# 05_RADIO.net
KiCad netlist of a schematic drawn in Altium Designer
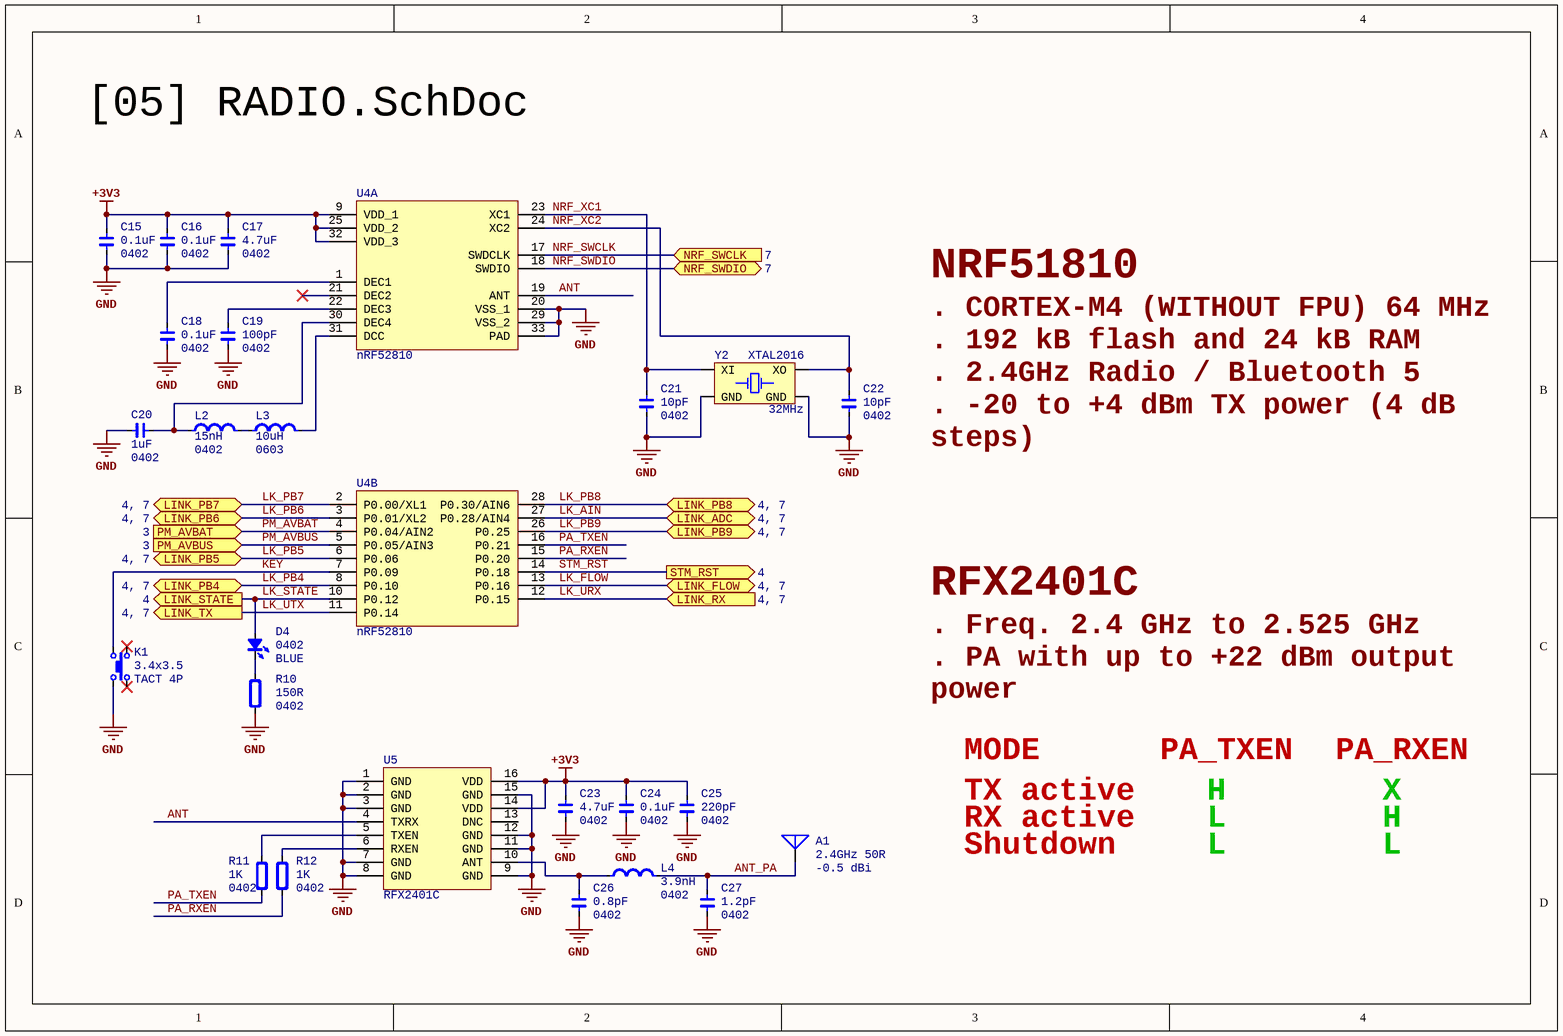
[diagram p0: [05] RADIO.SchDoc]

(export (version "E")
  (design (tool "Eeschema 10.0.6"))
  (components
    (comp (ref "A1")
      (value "2.4GHz 50R")
      (footprint "PCB_Antenna:ANT_2.4G_3.2x1.6")
      (description "Antenna")
      (fields (field (name "ALTIUM_VALUE") "-0.5 dBi"))
      (libsource (lib "SCH_Antenna") (part "Ant_2.4G"))
    )
    (comp (ref "C15")
      (value "0.1uF")
      (footprint "PCB_PassiveCap:CAP_0402")
      (description "Capacitor")
      (fields (field (name "TYPE") "0402") (field (name "Comment") "C0402"))
      (libsource (lib "SCH_Passive") (part "Cap_0402"))
    )
    (comp (ref "C16")
      (value "0.1uF")
      (footprint "PCB_PassiveCap:CAP_0402")
      (description "Capacitor")
      (fields (field (name "TYPE") "0402") (field (name "Comment") "C0402"))
      (libsource (lib "SCH_Passive") (part "Cap_0402"))
    )
    (comp (ref "C17")
      (value "4.7uF")
      (footprint "PCB_PassiveCap:CAP_0402")
      (description "Capacitor")
      (fields (field (name "TYPE") "0402") (field (name "Comment") "C0402"))
      (libsource (lib "SCH_Passive") (part "Cap_0402"))
    )
    (comp (ref "C18")
      (value "0.1uF")
      (footprint "PCB_PassiveCap:CAP_0402")
      (description "Capacitor")
      (fields (field (name "TYPE") "0402") (field (name "Comment") "C0402"))
      (libsource (lib "SCH_Passive") (part "Cap_0402"))
    )
    (comp (ref "C19")
      (value "100pF")
      (footprint "PCB_PassiveCap:CAP_0402")
      (description "Capacitor")
      (fields (field (name "TYPE") "0402") (field (name "Comment") "C0402"))
      (libsource (lib "SCH_Passive") (part "Cap_0402"))
    )
    (comp (ref "C20")
      (value "1uF")
      (footprint "PCB_PassiveCap:CAP_0402")
      (description "Capacitor")
      (fields (field (name "TYPE") "0402") (field (name "Comment") "C0402"))
      (libsource (lib "") (part "Cap_0402_1"))
    )
    (comp (ref "C21")
      (value "10pF")
      (footprint "PCB_PassiveCap:CAP_0402")
      (description "Capacitor")
      (fields (field (name "TYPE") "0402") (field (name "Comment") "C0402"))
      (libsource (lib "SCH_Passive") (part "Cap_0402"))
    )
    (comp (ref "C22")
      (value "10pF")
      (footprint "PCB_PassiveCap:CAP_0402")
      (description "Capacitor")
      (fields (field (name "TYPE") "0402") (field (name "Comment") "C0402"))
      (libsource (lib "SCH_Passive") (part "Cap_0402"))
    )
    (comp (ref "C23")
      (value "4.7uF")
      (footprint "PCB_PassiveCap:CAP_0402")
      (description "Capacitor")
      (fields (field (name "TYPE") "0402") (field (name "Comment") "C0402"))
      (libsource (lib "SCH_Passive") (part "Cap_0402"))
    )
    (comp (ref "C24")
      (value "0.1uF")
      (footprint "PCB_PassiveCap:CAP_0402")
      (description "Capacitor")
      (fields (field (name "TYPE") "0402") (field (name "Comment") "C0402"))
      (libsource (lib "SCH_Passive") (part "Cap_0402"))
    )
    (comp (ref "C25")
      (value "220pF")
      (footprint "PCB_PassiveCap:CAP_0402")
      (description "Capacitor")
      (fields (field (name "TYPE") "0402") (field (name "Comment") "C0402"))
      (libsource (lib "SCH_Passive") (part "Cap_0402"))
    )
    (comp (ref "C26")
      (value "0.8pF")
      (footprint "PCB_PassiveCap:CAP_0402")
      (description "Capacitor")
      (fields (field (name "TYPE") "0402") (field (name "Comment") "C0402"))
      (libsource (lib "SCH_Passive") (part "Cap_0402"))
    )
    (comp (ref "C27")
      (value "1.2pF")
      (footprint "PCB_PassiveCap:CAP_0402")
      (description "Capacitor")
      (fields (field (name "TYPE") "0402") (field (name "Comment") "C0402"))
      (libsource (lib "SCH_Passive") (part "Cap_0402"))
    )
    (comp (ref "D4")
      (value "BLUE")
      (footprint "PCB_ActiveLED:LED_0402_BLUE")
      (description "LED")
      (fields (field (name "TYPE") "0402"))
      (libsource (lib "SCH_Active") (part "LED_0402"))
    )
    (comp (ref "K1")
      (value "3.4x3.5")
      (footprint "PCB_Switch:ButtonTACT_3.4*3.5_90")
      (description "Button")
      (fields (field (name "TYPE") "TACT 4P") (field (name "Comment") "TACT 4P"))
      (libsource (lib "SCH_Switch") (part "ButtonTACT"))
    )
    (comp (ref "L2")
      (value "15nH")
      (footprint "PCB_PassiveInd:IND_0402")
      (description "Inductor")
      (fields (field (name "TYPE") "0402") (field (name "Comment") "H0402"))
      (libsource (lib "SCH_Passive") (part "Ind_0402"))
    )
    (comp (ref "L3")
      (value "10uH")
      (footprint "PCB_PassiveInd:IND_0603")
      (description "Inductor")
      (fields (field (name "TYPE") "0603") (field (name "Comment") "H0603"))
      (libsource (lib "SCH_Passive") (part "Ind_0603"))
    )
    (comp (ref "L4")
      (value "3.9nH")
      (footprint "PCB_PassiveInd:IND_0402")
      (description "Inductor")
      (fields (field (name "TYPE") "0402") (field (name "Comment") "H0402"))
      (libsource (lib "SCH_Passive") (part "Ind_0402"))
    )
    (comp (ref "R10")
      (value "150R")
      (footprint "PCB_PassiveRes:RES_0402")
      (description "Resistor")
      (fields (field (name "TYPE") "0402") (field (name "Comment") "R0402"))
      (libsource (lib "SCH_Passive") (part "Res_0402"))
    )
    (comp (ref "R11")
      (value "1K")
      (footprint "PCB_PassiveRes:RES_0402")
      (description "Resistor")
      (fields (field (name "TYPE") "0402") (field (name "Comment") "R0402"))
      (libsource (lib "SCH_Passive") (part "Res_0402"))
    )
    (comp (ref "R12")
      (value "1K")
      (footprint "PCB_PassiveRes:RES_0402")
      (description "Resistor")
      (fields (field (name "TYPE") "0402") (field (name "Comment") "R0402"))
      (libsource (lib "SCH_Passive") (part "Res_0402"))
    )
    (comp (ref "U4")
      (value "nRF52810")
      (footprint "PCB_IntegratedCircuit:QFN_P0.5_32")
      (description "MCU")
      (libsource (lib "SCH_IntegratedCircuit") (part "nRF52810"))
    )
    (comp (ref "U5")
      (value "RFX2401C")
      (footprint "PCB_IntegratedCircuit:QFN_P0.5_16")
      (description "Radio PA/LNA")
      (libsource (lib "SCH_IntegratedCircuit") (part "RFX2401C"))
    )
    (comp (ref "Y2")
      (value "32MHz")
      (footprint "PCB_Oscillator:XT_2016_4")
      (description "Crystal Oscillator")
      (fields (field (name "TYPE") "XTAL2016") (field (name "Comment") "XTAL2016"))
      (libsource (lib "SCH_Oscillator") (part "XTAL_2016_4P"))
    )
  )
  (nets
    (net (code "1") (name "+3V3") (class "Default")
      (node (ref "C15") (pin "2") (pinfunction "2_2") (pintype "passive"))
      (node (ref "C16") (pin "2") (pinfunction "2_2") (pintype "passive"))
      (node (ref "C17") (pin "2") (pinfunction "2_2") (pintype "passive"))
      (node (ref "C23") (pin "2") (pinfunction "2_2") (pintype "passive"))
      (node (ref "C24") (pin "2") (pinfunction "2_2") (pintype "passive"))
      (node (ref "C25") (pin "2") (pinfunction "2_2") (pintype "passive"))
      (node (ref "U4") (pin "25") (pinfunction "VDD_2_25") (pintype "passive"))
      (node (ref "U4") (pin "32") (pinfunction "VDD_3_32") (pintype "passive"))
      (node (ref "U4") (pin "9") (pinfunction "VDD_1_9") (pintype "passive"))
      (node (ref "U5") (pin "14") (pinfunction "VDD_14") (pintype "passive"))
      (node (ref "U5") (pin "16") (pinfunction "VDD_16") (pintype "passive"))
    )
    (net (code "2") (name "/ANT") (class "Default")
      (node (ref "U4") (pin "19") (pinfunction "ANT_19") (pintype "passive"))
      (node (ref "U5") (pin "4") (pinfunction "TXRX_4") (pintype "passive"))
    )
    (net (code "3") (name "/ANT_PA") (class "Default")
      (node (ref "A1") (pin "1") (pinfunction "A_1") (pintype "passive"))
      (node (ref "C27") (pin "2") (pinfunction "2_2") (pintype "passive"))
      (node (ref "L4") (pin "2") (pinfunction "2_2") (pintype "passive"))
    )
    (net (code "4") (name "/KEY") (class "Default")
      (node (ref "K1") (pin "2") (pinfunction "2_2") (pintype "passive"))
      (node (ref "U4") (pin "7") (pinfunction "P0.09_7") (pintype "passive"))
    )
    (net (code "5") (name "/LK_AIN") (class "Default")
      (node (ref "U4") (pin "27") (pinfunction "P0.28/AIN4_27") (pintype "passive"))
    )
    (net (code "6") (name "/LK_FLOW") (class "Default")
      (node (ref "U4") (pin "13") (pinfunction "P0.16_13") (pintype "passive"))
    )
    (net (code "7") (name "/LK_PB4") (class "Default")
      (node (ref "U4") (pin "8") (pinfunction "P0.10_8") (pintype "passive"))
    )
    (net (code "8") (name "/LK_PB5") (class "Default")
      (node (ref "U4") (pin "6") (pinfunction "P0.06_6") (pintype "passive"))
    )
    (net (code "9") (name "/LK_PB6") (class "Default")
      (node (ref "U4") (pin "3") (pinfunction "P0.01/XL2_3") (pintype "passive"))
    )
    (net (code "10") (name "/LK_PB7") (class "Default")
      (node (ref "U4") (pin "2") (pinfunction "P0.00/XL1_2") (pintype "passive"))
    )
    (net (code "11") (name "/LK_PB8") (class "Default")
      (node (ref "U4") (pin "28") (pinfunction "P0.30/AIN6_28") (pintype "passive"))
    )
    (net (code "12") (name "/LK_PB9") (class "Default")
      (node (ref "U4") (pin "26") (pinfunction "P0.25_26") (pintype "passive"))
    )
    (net (code "13") (name "/LK_STATE") (class "Default")
      (node (ref "D4") (pin "1") (pinfunction "A_1") (pintype "passive"))
      (node (ref "U4") (pin "10") (pinfunction "P0.12_10") (pintype "passive"))
    )
    (net (code "14") (name "/LK_URX") (class "Default")
      (node (ref "U4") (pin "12") (pinfunction "P0.15_12") (pintype "passive"))
    )
    (net (code "15") (name "/LK_UTX") (class "Default")
      (node (ref "U4") (pin "11") (pinfunction "P0.14_11") (pintype "passive"))
    )
    (net (code "16") (name "/NRF_SWCLK") (class "Default")
      (node (ref "U4") (pin "17") (pinfunction "SWDCLK_17") (pintype "passive"))
    )
    (net (code "17") (name "/NRF_SWDIO") (class "Default")
      (node (ref "U4") (pin "18") (pinfunction "SWDIO_18") (pintype "passive"))
    )
    (net (code "18") (name "/NRF_XC1") (class "Default")
      (node (ref "C21") (pin "2") (pinfunction "2_2") (pintype "passive"))
      (node (ref "U4") (pin "23") (pinfunction "XC1_23") (pintype "passive"))
      (node (ref "Y2") (pin "1") (pinfunction "XI_1") (pintype "passive"))
    )
    (net (code "19") (name "/NRF_XC2") (class "Default")
      (node (ref "C22") (pin "2") (pinfunction "2_2") (pintype "passive"))
      (node (ref "U4") (pin "24") (pinfunction "XC2_24") (pintype "passive"))
      (node (ref "Y2") (pin "3") (pinfunction "XO_3") (pintype "passive"))
    )
    (net (code "20") (name "/PA_RXEN") (class "Default")
      (node (ref "R12") (pin "1") (pinfunction "1_1") (pintype "passive"))
      (node (ref "U4") (pin "15") (pinfunction "P0.20_15") (pintype "passive"))
    )
    (net (code "21") (name "/PA_TXEN") (class "Default")
      (node (ref "R11") (pin "1") (pinfunction "1_1") (pintype "passive"))
      (node (ref "U4") (pin "16") (pinfunction "P0.21_16") (pintype "passive"))
    )
    (net (code "22") (name "/PM_AVBAT") (class "Default")
      (node (ref "U4") (pin "4") (pinfunction "P0.04/AIN2_4") (pintype "passive"))
    )
    (net (code "23") (name "/PM_AVBUS") (class "Default")
      (node (ref "U4") (pin "5") (pinfunction "P0.05/AIN3_5") (pintype "passive"))
    )
    (net (code "24") (name "/STM_RST") (class "Default")
      (node (ref "U4") (pin "14") (pinfunction "P0.18_14") (pintype "passive"))
    )
    (net (code "25") (name "GND") (class "Default")
      (node (ref "C15") (pin "1") (pinfunction "1_1") (pintype "passive"))
      (node (ref "C16") (pin "1") (pinfunction "1_1") (pintype "passive"))
      (node (ref "C17") (pin "1") (pinfunction "1_1") (pintype "passive"))
      (node (ref "C18") (pin "1") (pinfunction "1_1") (pintype "passive"))
      (node (ref "C19") (pin "1") (pinfunction "1_1") (pintype "passive"))
      (node (ref "C20") (pin "2") (pinfunction "2_2") (pintype "passive"))
      (node (ref "C21") (pin "1") (pinfunction "1_1") (pintype "passive"))
      (node (ref "C22") (pin "1") (pinfunction "1_1") (pintype "passive"))
      (node (ref "C23") (pin "1") (pinfunction "1_1") (pintype "passive"))
      (node (ref "C24") (pin "1") (pinfunction "1_1") (pintype "passive"))
      (node (ref "C25") (pin "1") (pinfunction "1_1") (pintype "passive"))
      (node (ref "C26") (pin "1") (pinfunction "1_1") (pintype "passive"))
      (node (ref "C27") (pin "1") (pinfunction "1_1") (pintype "passive"))
      (node (ref "K1") (pin "1") (pinfunction "1_1") (pintype "passive"))
      (node (ref "R10") (pin "1") (pinfunction "1_1") (pintype "passive"))
      (node (ref "U4") (pin "20") (pinfunction "VSS_1_20") (pintype "passive"))
      (node (ref "U4") (pin "29") (pinfunction "VSS_2_29") (pintype "passive"))
      (node (ref "U4") (pin "33") (pinfunction "PAD_33") (pintype "passive"))
      (node (ref "U5") (pin "1") (pinfunction "GND_1") (pintype "passive"))
      (node (ref "U5") (pin "11") (pinfunction "GND_11") (pintype "passive"))
      (node (ref "U5") (pin "12") (pinfunction "GND_12") (pintype "passive"))
      (node (ref "U5") (pin "15") (pinfunction "GND_15") (pintype "passive"))
      (node (ref "U5") (pin "2") (pinfunction "GND_2") (pintype "passive"))
      (node (ref "U5") (pin "3") (pinfunction "GND_3") (pintype "passive"))
      (node (ref "U5") (pin "7") (pinfunction "GND_7") (pintype "passive"))
      (node (ref "U5") (pin "8") (pinfunction "GND_8") (pintype "passive"))
      (node (ref "U5") (pin "9") (pinfunction "GND_9") (pintype "passive"))
      (node (ref "Y2") (pin "2") (pinfunction "GND_2") (pintype "passive"))
      (node (ref "Y2") (pin "4") (pinfunction "GND_4") (pintype "passive"))
    )
    (net (code "26") (name "Net-(D4-K)") (class "Default")
      (node (ref "D4") (pin "2") (pinfunction "K_2") (pintype "passive"))
      (node (ref "R10") (pin "2") (pinfunction "2_2") (pintype "passive"))
    )
    (net (code "27") (name "Net-(L2-Pad2)") (class "Default")
      (node (ref "L2") (pin "2") (pinfunction "2_2") (pintype "passive"))
      (node (ref "L3") (pin "1") (pinfunction "1_1") (pintype "passive"))
    )
    (net (code "28") (name "Net-(U4A-DCC)") (class "Default")
      (node (ref "L3") (pin "2") (pinfunction "2_2") (pintype "passive"))
      (node (ref "U4") (pin "31") (pinfunction "DCC_31") (pintype "passive"))
    )
    (net (code "29") (name "Net-(U4A-DEC1)") (class "Default")
      (node (ref "C18") (pin "2") (pinfunction "2_2") (pintype "passive"))
      (node (ref "U4") (pin "1") (pinfunction "DEC1_1") (pintype "passive"))
    )
    (net (code "30") (name "Net-(U4A-DEC3)") (class "Default")
      (node (ref "C19") (pin "2") (pinfunction "2_2") (pintype "passive"))
      (node (ref "U4") (pin "22") (pinfunction "DEC3_22") (pintype "passive"))
    )
    (net (code "31") (name "Net-(U4A-DEC4)") (class "Default")
      (node (ref "C20") (pin "1") (pinfunction "1_1") (pintype "passive"))
      (node (ref "L2") (pin "1") (pinfunction "1_1") (pintype "passive"))
      (node (ref "U4") (pin "30") (pinfunction "DEC4_30") (pintype "passive"))
    )
    (net (code "32") (name "Net-(U5-ANT)") (class "Default")
      (node (ref "C26") (pin "2") (pinfunction "2_2") (pintype "passive"))
      (node (ref "L4") (pin "1") (pinfunction "1_1") (pintype "passive"))
      (node (ref "U5") (pin "10") (pinfunction "ANT_10") (pintype "passive"))
    )
    (net (code "33") (name "Net-(U5-RXEN)") (class "Default")
      (node (ref "R12") (pin "2") (pinfunction "2_2") (pintype "passive"))
      (node (ref "U5") (pin "6") (pinfunction "RXEN_6") (pintype "passive"))
    )
    (net (code "34") (name "Net-(U5-TXEN)") (class "Default")
      (node (ref "R11") (pin "2") (pinfunction "2_2") (pintype "passive"))
      (node (ref "U5") (pin "5") (pinfunction "TXEN_5") (pintype "passive"))
    )
    (net (code "35") (name "unconnected-(K1-Pad3)") (class "Default")
      (node (ref "K1") (pin "3") (pinfunction "3_3") (pintype "passive+no_connect"))
    )
    (net (code "36") (name "unconnected-(K1-Pad4)") (class "Default")
      (node (ref "K1") (pin "4") (pinfunction "4_4") (pintype "passive+no_connect"))
    )
    (net (code "37") (name "unconnected-(U4A-DEC2-Pad21)") (class "Default")
      (node (ref "U4") (pin "21") (pinfunction "DEC2_21") (pintype "passive+no_connect"))
    )
    (net (code "38") (name "unconnected-(U5-DNC-Pad13)") (class "Default")
      (node (ref "U5") (pin "13") (pinfunction "DNC_13") (pintype "passive"))
    )
  )
)
